# improved-handheld-turbidimeter_TIA_proto.net
KiCad netlist of a schematic drawn in EAGLE
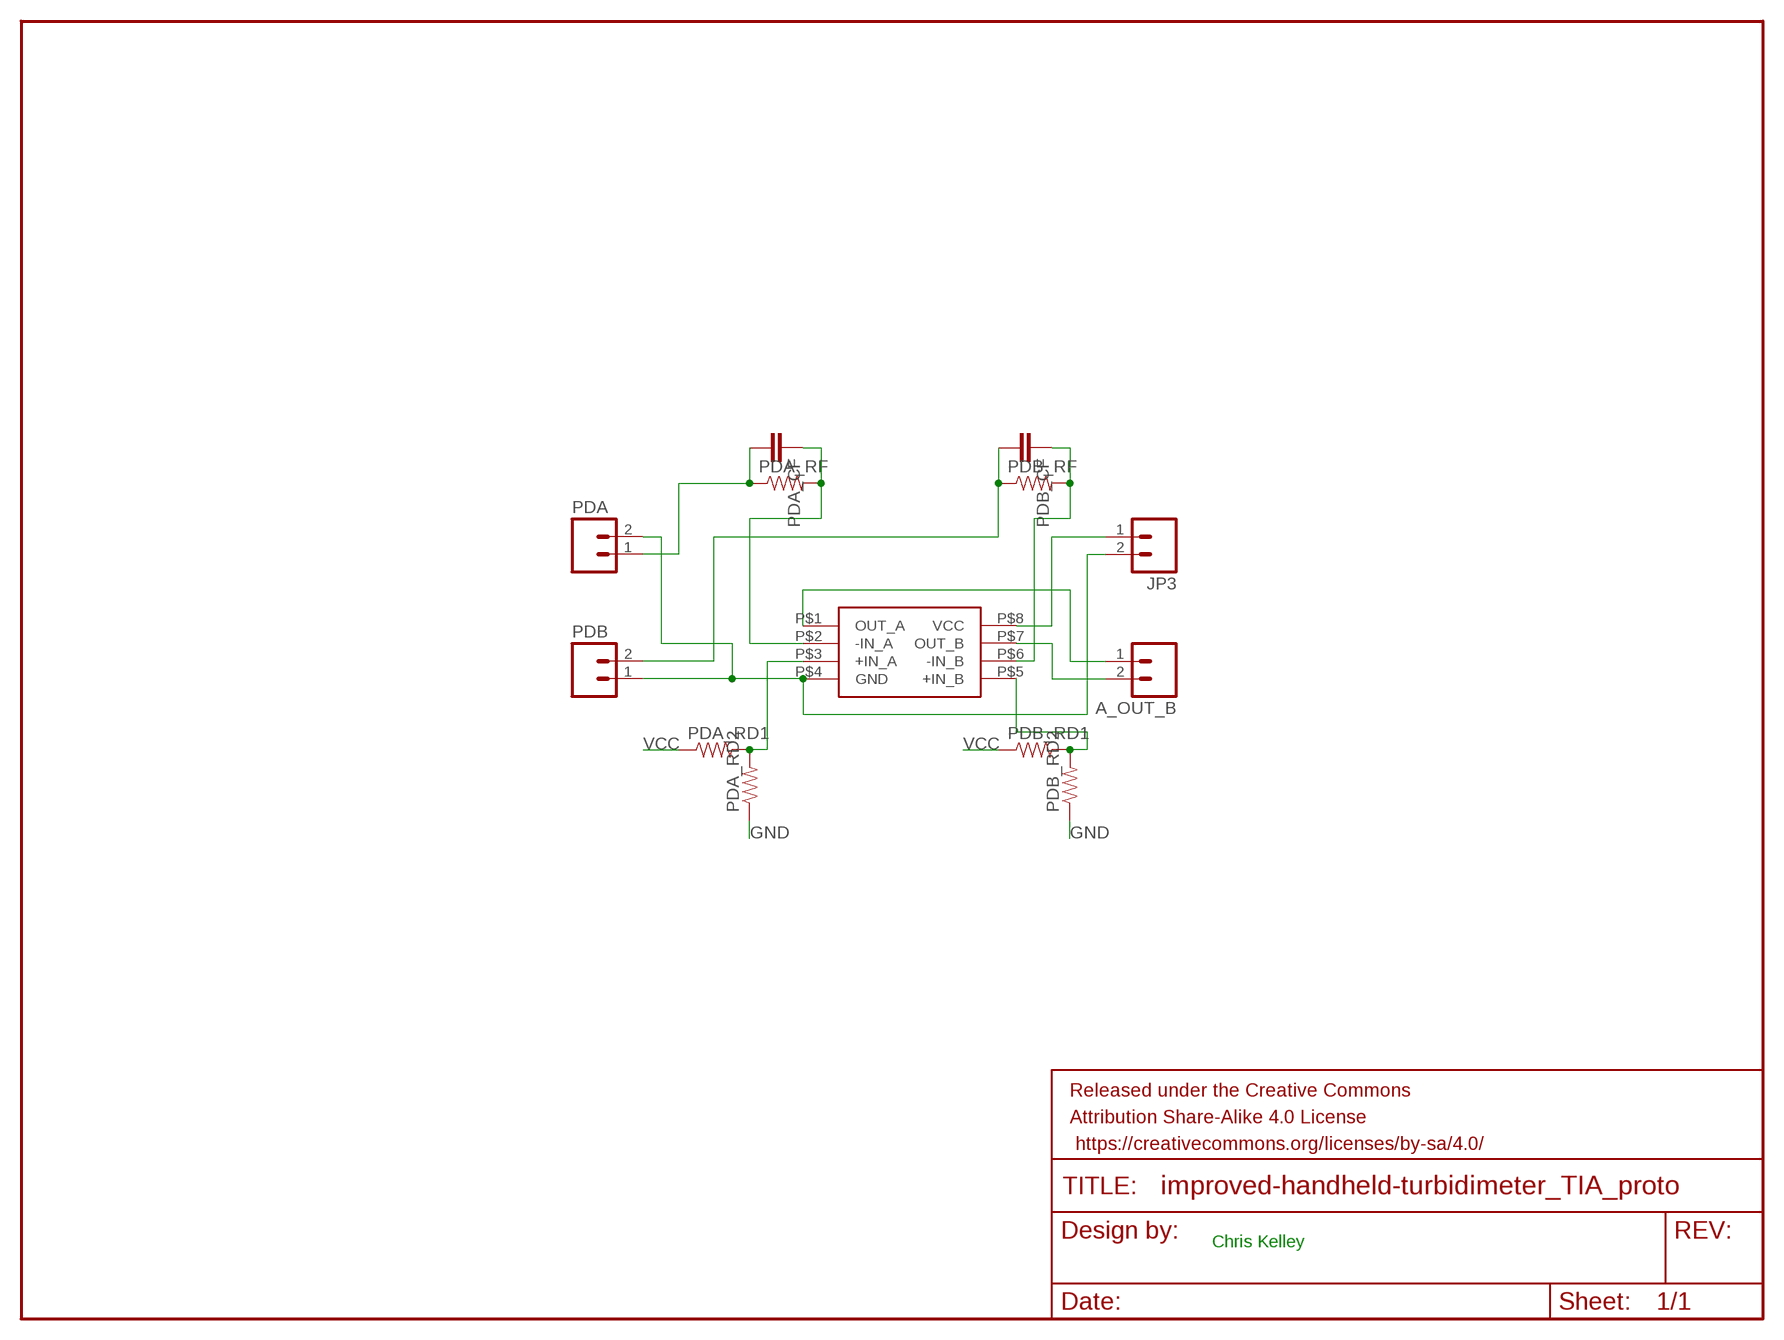
[diagram p0: schematic, sheet 1]

(export (version "E")
  (design (tool "Eeschema 10.0.6"))
  (components
    (comp (ref "A_OUT_B")
      (value "M02PTH")
      (footprint "eagle-import:1X02")
      (libsource (lib "eagle-import") (part "M02PTH"))
    )
    (comp (ref "FRAME1")
      (value "FRAME-LETTER")
      (footprint "eagle-import:CREATIVE_COMMONS")
      (libsource (lib "eagle-import") (part "FRAME-LETTER"))
    )
    (comp (ref "JP3")
      (value "M02PTH")
      (footprint "eagle-import:1X02")
      (libsource (lib "eagle-import") (part "M02PTH"))
    )
    (comp (ref "PDA")
      (value "M02PTH")
      (footprint "eagle-import:1X02")
      (libsource (lib "eagle-import") (part "M02PTH"))
    )
    (comp (ref "PDA_CF")
      (value "CAP0603-CAP")
      (footprint "eagle-import:0603-CAP")
      (libsource (lib "eagle-import") (part "CAP0603-CAP"))
    )
    (comp (ref "PDA_RD1")
      (value "RESISTOR0603-RES")
      (footprint "eagle-import:0603-RES")
      (libsource (lib "eagle-import") (part "RESISTOR0603-RES"))
    )
    (comp (ref "PDA_RD2")
      (value "RESISTOR0603-RES")
      (footprint "eagle-import:0603-RES")
      (libsource (lib "eagle-import") (part "RESISTOR0603-RES"))
    )
    (comp (ref "PDA_RF")
      (value "RESISTOR0603-RES")
      (footprint "eagle-import:0603-RES")
      (libsource (lib "eagle-import") (part "RESISTOR0603-RES"))
    )
    (comp (ref "PDB")
      (value "M02PTH")
      (footprint "eagle-import:1X02")
      (libsource (lib "eagle-import") (part "M02PTH"))
    )
    (comp (ref "PDB_CF")
      (value "CAP0603-CAP")
      (footprint "eagle-import:0603-CAP")
      (libsource (lib "eagle-import") (part "CAP0603-CAP"))
    )
    (comp (ref "PDB_RD1")
      (value "RESISTOR0603-RES")
      (footprint "eagle-import:0603-RES")
      (libsource (lib "eagle-import") (part "RESISTOR0603-RES"))
    )
    (comp (ref "PDB_RD2")
      (value "RESISTOR0603-RES")
      (footprint "eagle-import:0603-RES")
      (libsource (lib "eagle-import") (part "RESISTOR0603-RES"))
    )
    (comp (ref "PDB_RF")
      (value "RESISTOR0603-RES")
      (footprint "eagle-import:0603-RES")
      (libsource (lib "eagle-import") (part "RESISTOR0603-RES"))
    )
    (comp (ref "U$2")
      (value "ADA4528-2")
      (footprint "eagle-import:ADA4528-2")
      (libsource (lib "eagle-import") (part "ADA4528-2"))
    )
  )
  (nets
    (net (code "1") (name "/GND") (class "Default")
      (node (ref "JP3") (pin "2") (pinfunction "2_2") (pintype "passive"))
      (node (ref "PDA") (pin "2") (pinfunction "2_2") (pintype "passive"))
      (node (ref "PDA_RD2") (pin "1") (pinfunction "1_1") (pintype "passive"))
      (node (ref "PDB") (pin "1") (pinfunction "1_1") (pintype "passive"))
      (node (ref "PDB_RD2") (pin "1") (pinfunction "1_1") (pintype "passive"))
      (node (ref "U$2") (pin "P$4") (pinfunction "GND_P$4") (pintype "bidirectional"))
    )
    (net (code "2") (name "/VCC") (class "Default")
      (node (ref "JP3") (pin "1") (pinfunction "1_1") (pintype "passive"))
      (node (ref "PDA_RD1") (pin "1") (pinfunction "1_1") (pintype "passive"))
      (node (ref "PDB_RD1") (pin "1") (pinfunction "1_1") (pintype "passive"))
      (node (ref "U$2") (pin "P$8") (pinfunction "VCC_P$8") (pintype "bidirectional"))
    )
    (net (code "3") (name "Net-(PDA-Pad1)") (class "Default")
      (node (ref "PDA") (pin "1") (pinfunction "1_1") (pintype "passive"))
      (node (ref "PDA_CF") (pin "2") (pinfunction "2_2") (pintype "passive"))
      (node (ref "PDA_RF") (pin "1") (pinfunction "1_1") (pintype "passive"))
    )
    (net (code "4") (name "Net-(PDB-Pad2)") (class "Default")
      (node (ref "PDB") (pin "2") (pinfunction "2_2") (pintype "passive"))
      (node (ref "PDB_CF") (pin "2") (pinfunction "2_2") (pintype "passive"))
      (node (ref "PDB_RF") (pin "1") (pinfunction "1_1") (pintype "passive"))
    )
    (net (code "5") (name "Net-(U$2-+IN_A)") (class "Default")
      (node (ref "PDA_RD1") (pin "2") (pinfunction "2_2") (pintype "passive"))
      (node (ref "PDA_RD2") (pin "2") (pinfunction "2_2") (pintype "passive"))
      (node (ref "U$2") (pin "P$3") (pinfunction "+IN_A_P$3") (pintype "bidirectional"))
    )
    (net (code "6") (name "Net-(U$2-+IN_B)") (class "Default")
      (node (ref "PDB_RD1") (pin "2") (pinfunction "2_2") (pintype "passive"))
      (node (ref "PDB_RD2") (pin "2") (pinfunction "2_2") (pintype "passive"))
      (node (ref "U$2") (pin "P$5") (pinfunction "+IN_B_P$5") (pintype "bidirectional"))
    )
    (net (code "7") (name "Net-(U$2--IN_A)") (class "Default")
      (node (ref "PDA_CF") (pin "1") (pinfunction "1_1") (pintype "passive"))
      (node (ref "PDA_RF") (pin "2") (pinfunction "2_2") (pintype "passive"))
      (node (ref "U$2") (pin "P$2") (pinfunction "-IN_A_P$2") (pintype "bidirectional"))
    )
    (net (code "8") (name "Net-(U$2--IN_B)") (class "Default")
      (node (ref "PDB_CF") (pin "1") (pinfunction "1_1") (pintype "passive"))
      (node (ref "PDB_RF") (pin "2") (pinfunction "2_2") (pintype "passive"))
      (node (ref "U$2") (pin "P$6") (pinfunction "-IN_B_P$6") (pintype "bidirectional"))
    )
    (net (code "9") (name "Net-(U$2-OUT_A)") (class "Default")
      (node (ref "A_OUT_B") (pin "1") (pinfunction "1_1") (pintype "passive"))
      (node (ref "U$2") (pin "P$1") (pinfunction "OUT_A_P$1") (pintype "bidirectional"))
    )
    (net (code "10") (name "Net-(U$2-OUT_B)") (class "Default")
      (node (ref "A_OUT_B") (pin "2") (pinfunction "2_2") (pintype "passive"))
      (node (ref "U$2") (pin "P$7") (pinfunction "OUT_B_P$7") (pintype "bidirectional"))
    )
  )
)
